# out.net
KiCad netlist of a schematic drawn in EAGLE
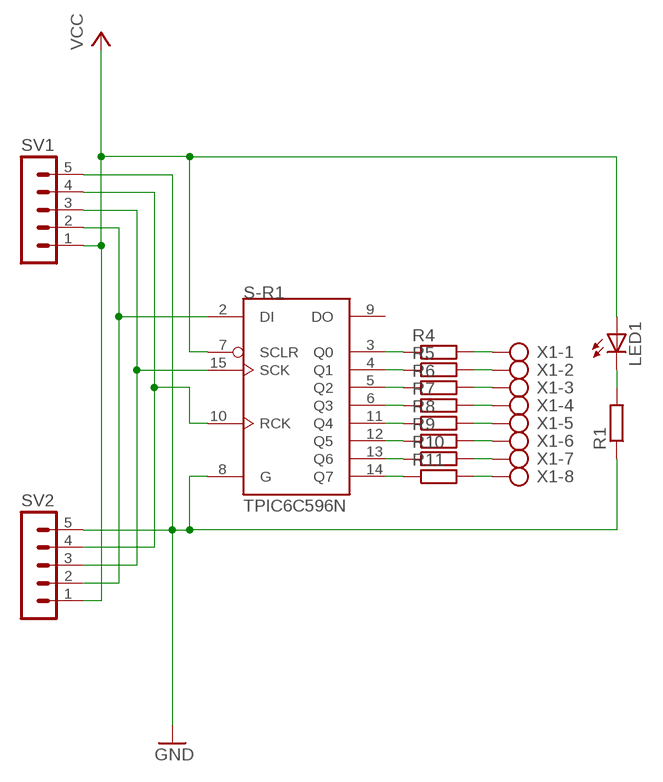
[diagram p0: schematic, sheet 1]

(export (version "E")
  (design (tool "Eeschema 10.0.6"))
  (components
    (comp (ref "LED1")
      (value "LED3MM")
      (footprint "eagle-import:LED3MM")
      (libsource (lib "eagle-import") (part "LED3MM"))
    )
    (comp (ref "R1")
      (value "R-EU_0207/2V")
      (footprint "eagle-import:0207_2V")
      (libsource (lib "eagle-import") (part "R-EU_0207/2V"))
    )
    (comp (ref "R4")
      (value "R-EU_0207/2V")
      (footprint "eagle-import:0207_2V")
      (libsource (lib "eagle-import") (part "R-EU_0207/2V"))
    )
    (comp (ref "R5")
      (value "R-EU_0207/2V")
      (footprint "eagle-import:0207_2V")
      (libsource (lib "eagle-import") (part "R-EU_0207/2V"))
    )
    (comp (ref "R6")
      (value "R-EU_0207/2V")
      (footprint "eagle-import:0207_2V")
      (libsource (lib "eagle-import") (part "R-EU_0207/2V"))
    )
    (comp (ref "R7")
      (value "R-EU_0207/2V")
      (footprint "eagle-import:0207_2V")
      (libsource (lib "eagle-import") (part "R-EU_0207/2V"))
    )
    (comp (ref "R8")
      (value "R-EU_0207/2V")
      (footprint "eagle-import:0207_2V")
      (libsource (lib "eagle-import") (part "R-EU_0207/2V"))
    )
    (comp (ref "R9")
      (value "R-EU_0207/2V")
      (footprint "eagle-import:0207_2V")
      (libsource (lib "eagle-import") (part "R-EU_0207/2V"))
    )
    (comp (ref "R10")
      (value "R-EU_0207/2V")
      (footprint "eagle-import:0207_2V")
      (libsource (lib "eagle-import") (part "R-EU_0207/2V"))
    )
    (comp (ref "R11")
      (value "R-EU_0207/2V")
      (footprint "eagle-import:0207_2V")
      (libsource (lib "eagle-import") (part "R-EU_0207/2V"))
    )
    (comp (ref "S-R1")
      (value "TPIC6C596N")
      (footprint "eagle-import:DIL16")
      (libsource (lib "eagle-import") (part "TPIC6C596N"))
    )
    (comp (ref "SV1")
      (value "MA05-1")
      (footprint "eagle-import:MA05-1")
      (libsource (lib "eagle-import") (part "MA05-1"))
    )
    (comp (ref "SV2")
      (value "MA05-1")
      (footprint "eagle-import:MA05-1")
      (libsource (lib "eagle-import") (part "MA05-1"))
    )
    (comp (ref "X1")
      (value "AK500/8-H")
      (footprint "eagle-import:AK500_8-H")
      (libsource (lib "eagle-import") (part "AK500/8-H"))
    )
  )
  (nets
    (net (code "1") (name "GND") (class "Default")
      (node (ref "R1") (pin "1") (pinfunction "1_1") (pintype "passive"))
      (node (ref "S-R1") (pin "8") (pinfunction "G_8") (pintype "input"))
      (node (ref "SV1") (pin "5") (pinfunction "5_5") (pintype "passive"))
      (node (ref "SV2") (pin "5") (pinfunction "5_5") (pintype "passive"))
    )
    (net (code "2") (name "Net-(LED1-C)") (class "Default")
      (node (ref "LED1") (pin "K") (pinfunction "C_K") (pintype "passive"))
      (node (ref "R1") (pin "2") (pinfunction "2_2") (pintype "passive"))
    )
    (net (code "3") (name "Net-(S-R1A-DI)") (class "Default")
      (node (ref "S-R1") (pin "2") (pinfunction "DI_2") (pintype "input"))
      (node (ref "SV1") (pin "2") (pinfunction "2_2") (pintype "passive"))
      (node (ref "SV2") (pin "2") (pinfunction "2_2") (pintype "passive"))
    )
    (net (code "4") (name "Net-(S-R1A-Q0)") (class "Default")
      (node (ref "R4") (pin "1") (pinfunction "1_1") (pintype "passive"))
      (node (ref "S-R1") (pin "3") (pinfunction "Q0_3") (pintype "open_collector"))
    )
    (net (code "5") (name "Net-(S-R1A-Q1)") (class "Default")
      (node (ref "R5") (pin "1") (pinfunction "1_1") (pintype "passive"))
      (node (ref "S-R1") (pin "4") (pinfunction "Q1_4") (pintype "open_collector"))
    )
    (net (code "6") (name "Net-(S-R1A-Q2)") (class "Default")
      (node (ref "R6") (pin "1") (pinfunction "1_1") (pintype "passive"))
      (node (ref "S-R1") (pin "5") (pinfunction "Q2_5") (pintype "open_collector"))
    )
    (net (code "7") (name "Net-(S-R1A-Q3)") (class "Default")
      (node (ref "R7") (pin "1") (pinfunction "1_1") (pintype "passive"))
      (node (ref "S-R1") (pin "6") (pinfunction "Q3_6") (pintype "open_collector"))
    )
    (net (code "8") (name "Net-(S-R1A-Q4)") (class "Default")
      (node (ref "R8") (pin "1") (pinfunction "1_1") (pintype "passive"))
      (node (ref "S-R1") (pin "11") (pinfunction "Q4_11") (pintype "open_collector"))
    )
    (net (code "9") (name "Net-(S-R1A-Q5)") (class "Default")
      (node (ref "R9") (pin "1") (pinfunction "1_1") (pintype "passive"))
      (node (ref "S-R1") (pin "12") (pinfunction "Q5_12") (pintype "open_collector"))
    )
    (net (code "10") (name "Net-(S-R1A-Q6)") (class "Default")
      (node (ref "R10") (pin "1") (pinfunction "1_1") (pintype "passive"))
      (node (ref "S-R1") (pin "13") (pinfunction "Q6_13") (pintype "open_collector"))
    )
    (net (code "11") (name "Net-(S-R1A-Q7)") (class "Default")
      (node (ref "R11") (pin "1") (pinfunction "1_1") (pintype "passive"))
      (node (ref "S-R1") (pin "14") (pinfunction "Q7_14") (pintype "open_collector"))
    )
    (net (code "12") (name "Net-(S-R1A-RCK)") (class "Default")
      (node (ref "S-R1") (pin "10") (pinfunction "RCK_10") (pintype "input"))
      (node (ref "SV1") (pin "4") (pinfunction "4_4") (pintype "passive"))
      (node (ref "SV2") (pin "4") (pinfunction "4_4") (pintype "passive"))
    )
    (net (code "13") (name "Net-(S-R1A-SCK)") (class "Default")
      (node (ref "S-R1") (pin "15") (pinfunction "SCK_15") (pintype "input"))
      (node (ref "SV1") (pin "3") (pinfunction "3_3") (pintype "passive"))
      (node (ref "SV2") (pin "3") (pinfunction "3_3") (pintype "passive"))
    )
    (net (code "14") (name "Net-(X1A-KL)") (class "Default")
      (node (ref "R4") (pin "2") (pinfunction "2_2") (pintype "passive"))
      (node (ref "X1") (pin "1") (pinfunction "KL_1") (pintype "passive"))
    )
    (net (code "15") (name "Net-(X1B-KL)") (class "Default")
      (node (ref "R5") (pin "2") (pinfunction "2_2") (pintype "passive"))
      (node (ref "X1") (pin "2") (pinfunction "KL_2") (pintype "passive"))
    )
    (net (code "16") (name "Net-(X1C-KL)") (class "Default")
      (node (ref "R6") (pin "2") (pinfunction "2_2") (pintype "passive"))
      (node (ref "X1") (pin "3") (pinfunction "KL_3") (pintype "passive"))
    )
    (net (code "17") (name "Net-(X1D-KL)") (class "Default")
      (node (ref "R7") (pin "2") (pinfunction "2_2") (pintype "passive"))
      (node (ref "X1") (pin "4") (pinfunction "KL_4") (pintype "passive"))
    )
    (net (code "18") (name "Net-(X1E-KL)") (class "Default")
      (node (ref "R8") (pin "2") (pinfunction "2_2") (pintype "passive"))
      (node (ref "X1") (pin "5") (pinfunction "KL_5") (pintype "passive"))
    )
    (net (code "19") (name "Net-(X1F-KL)") (class "Default")
      (node (ref "R9") (pin "2") (pinfunction "2_2") (pintype "passive"))
      (node (ref "X1") (pin "6") (pinfunction "KL_6") (pintype "passive"))
    )
    (net (code "20") (name "Net-(X1G-KL)") (class "Default")
      (node (ref "R10") (pin "2") (pinfunction "2_2") (pintype "passive"))
      (node (ref "X1") (pin "7") (pinfunction "KL_7") (pintype "passive"))
    )
    (net (code "21") (name "Net-(X1H-KL)") (class "Default")
      (node (ref "R11") (pin "2") (pinfunction "2_2") (pintype "passive"))
      (node (ref "X1") (pin "8") (pinfunction "KL_8") (pintype "passive"))
    )
    (net (code "22") (name "VCC") (class "Default")
      (node (ref "LED1") (pin "A") (pinfunction "A_A") (pintype "passive"))
      (node (ref "S-R1") (pin "7") (pinfunction "SCLR_7") (pintype "input"))
      (node (ref "SV1") (pin "1") (pinfunction "1_1") (pintype "passive"))
      (node (ref "SV2") (pin "1") (pinfunction "1_1") (pintype "passive"))
    )
    (net (code "23") (name "unconnected-(S-R1A-DO-Pad9)") (class "Default")
      (node (ref "S-R1") (pin "9") (pinfunction "DO_9") (pintype "output"))
    )
  )
)
